# DAC_and_MIC.net
KiCad netlist of a schematic drawn in Altium Designer
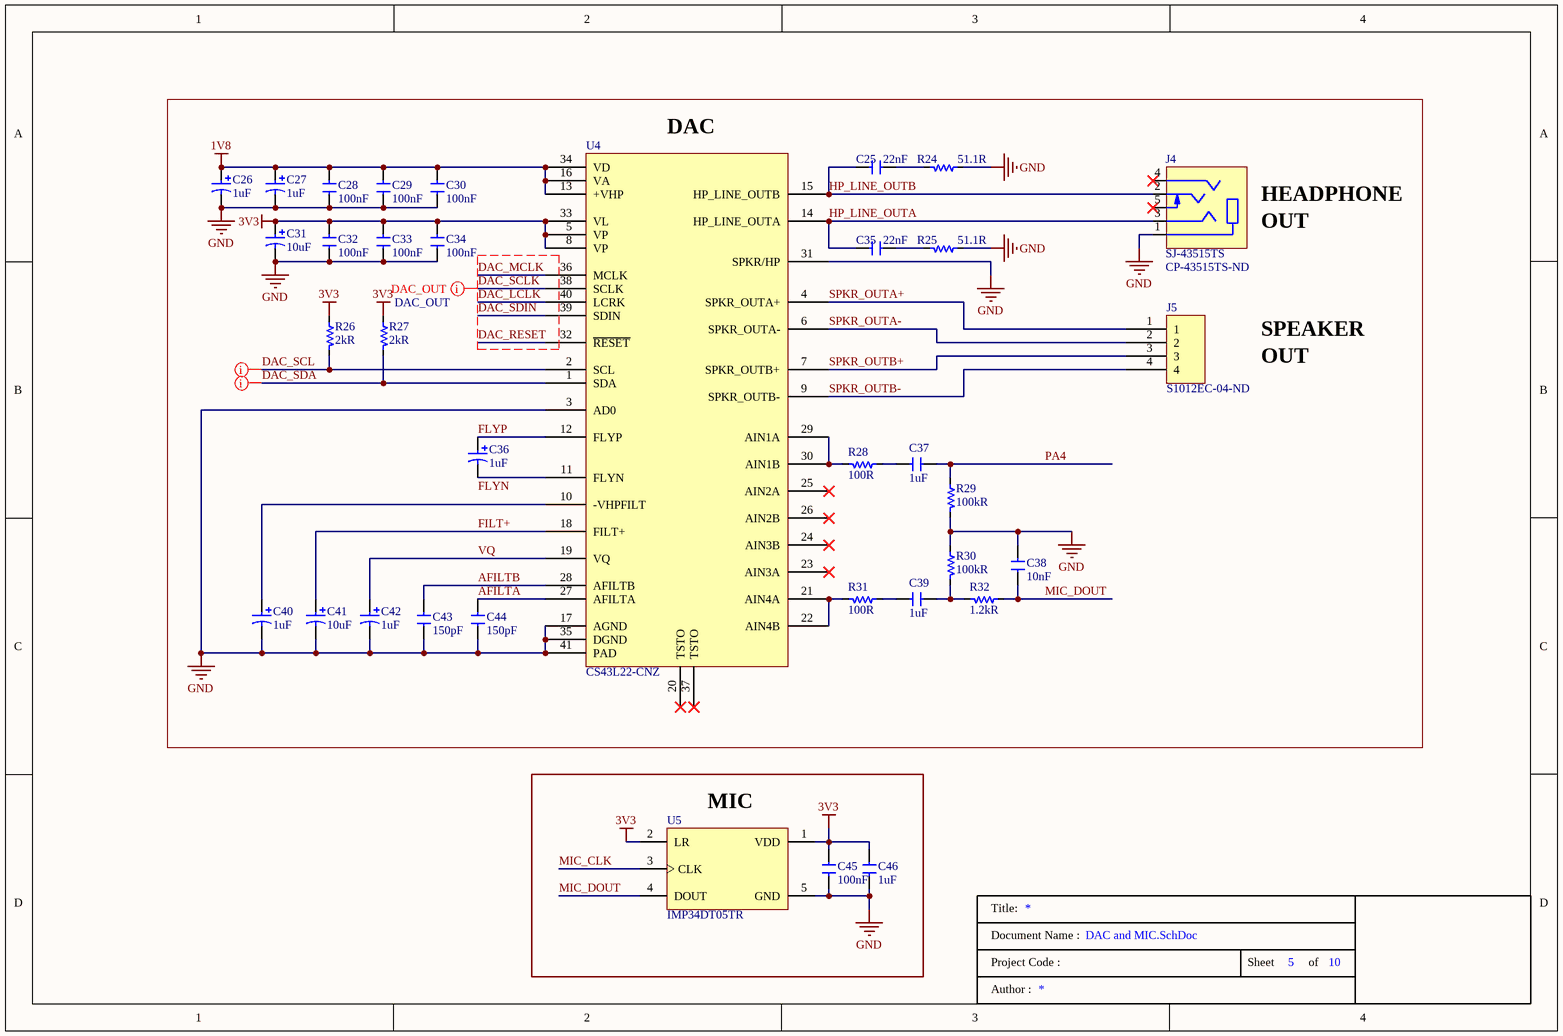
[diagram p0: DAC and MIC.SchDoc]

(export (version "E")
  (design (tool "Eeschema 10.0.6"))
  (components
    (comp (ref "C25")
      (value "CAP_22nF_50V_0805_X7R_CER")
      (footprint "0805_CAP")
      (description "Cap Ceramic 0.022uF 50V X7R 10% Pad SMD 0805 125C T/R")
      (fields
        (field (name "MANUFACTURER") "KEMET")
        (field (name "MANUFACTURER PART NUMBER") "C0805C223K5RAC7210")
        (field (name "CAPACITANCE") "22nF")
      )
      (libsource (lib "Main Component Library") (part "CAP_22nF_50V_0805_X7R_CER"))
    )
    (comp (ref "C26")
      (value "CAP_1uF_10%_16V_1206_TANT")
      (footprint "1206_TANT_CAP")
      (description "CAP TANT 1UF 10% 16V 1206")
      (fields
        (field (name "MANUFACTURER") "Kyocera AVX")
        (field (name "MANUFACTURER PART NUMBER") "TAJA105K016SNJ")
        (field (name "CAPACITANCE") "1uF")
      )
      (libsource (lib "Main Component Library") (part "CAP_1uF_10%_16V_1206_TANT"))
    )
    (comp (ref "C27")
      (value "CAP_1uF_10%_16V_1206_TANT")
      (footprint "1206_TANT_CAP")
      (description "CAP TANT 1UF 10% 16V 1206")
      (fields
        (field (name "MANUFACTURER") "Kyocera AVX")
        (field (name "MANUFACTURER PART NUMBER") "TAJA105K016SNJ")
        (field (name "CAPACITANCE") "1uF")
      )
      (libsource (lib "Main Component Library") (part "CAP_1uF_10%_16V_1206_TANT"))
    )
    (comp (ref "C28")
      (value "CAP_0.1uF_50V_0805_X7R_CER")
      (footprint "0805_CAP")
      (description "Cap Ceramic 0.1uF 50V X7R 20% SMD 0805 125C Paper T/R")
      (fields
        (field (name "MANUFACTURER") "KEMET")
        (field (name "MANUFACTURER PART NUMBER") "C0805C104M5RACTU")
        (field (name "CAPACITANCE") "100nF")
      )
      (libsource (lib "Main Component Library") (part "CAP_0.1uF_50V_0805_X7R_CER"))
    )
    (comp (ref "C29")
      (value "CAP_0.1uF_50V_0805_X7R_CER")
      (footprint "0805_CAP")
      (description "Cap Ceramic 0.1uF 50V X7R 20% SMD 0805 125C Paper T/R")
      (fields
        (field (name "MANUFACTURER") "KEMET")
        (field (name "MANUFACTURER PART NUMBER") "C0805C104M5RACTU")
        (field (name "CAPACITANCE") "100nF")
      )
      (libsource (lib "Main Component Library") (part "CAP_0.1uF_50V_0805_X7R_CER"))
    )
    (comp (ref "C30")
      (value "CAP_0.1uF_50V_0805_X7R_CER")
      (footprint "0805_CAP")
      (description "Cap Ceramic 0.1uF 50V X7R 20% SMD 0805 125C Paper T/R")
      (fields
        (field (name "MANUFACTURER") "KEMET")
        (field (name "MANUFACTURER PART NUMBER") "C0805C104M5RACTU")
        (field (name "CAPACITANCE") "100nF")
      )
      (libsource (lib "Main Component Library") (part "CAP_0.1uF_50V_0805_X7R_CER"))
    )
    (comp (ref "C31")
      (value "CAP_10uF_10V_10%_1206_TANT")
      (footprint "1206_TANT_CAP")
      (description "Cap Tant Solid 10uF 10V A CASE 10% (3.2 X 1.6 X 1.6mm) Inward L SMD 3216-18 3 Ohm 125C T/R")
      (fields
        (field (name "MANUFACTURER") "Kyocera AVX")
        (field (name "MANUFACTURER PART NUMBER") "TAJA106K010SNJ")
        (field (name "CAPACITANCE") "10uF")
      )
      (libsource (lib "Main Component Library") (part "CAP_10uF_10V_10%_1206_TANT"))
    )
    (comp (ref "C32")
      (value "CAP_0.1uF_50V_0805_X7R_CER")
      (footprint "0805_CAP")
      (description "Cap Ceramic 0.1uF 50V X7R 20% SMD 0805 125C Paper T/R")
      (fields
        (field (name "MANUFACTURER") "KEMET")
        (field (name "MANUFACTURER PART NUMBER") "C0805C104M5RACTU")
        (field (name "CAPACITANCE") "100nF")
      )
      (libsource (lib "Main Component Library") (part "CAP_0.1uF_50V_0805_X7R_CER"))
    )
    (comp (ref "C33")
      (value "CAP_0.1uF_50V_0805_X7R_CER")
      (footprint "0805_CAP")
      (description "Cap Ceramic 0.1uF 50V X7R 20% SMD 0805 125C Paper T/R")
      (fields
        (field (name "MANUFACTURER") "KEMET")
        (field (name "MANUFACTURER PART NUMBER") "C0805C104M5RACTU")
        (field (name "CAPACITANCE") "100nF")
      )
      (libsource (lib "Main Component Library") (part "CAP_0.1uF_50V_0805_X7R_CER"))
    )
    (comp (ref "C34")
      (value "CAP_0.1uF_50V_0805_X7R_CER")
      (footprint "0805_CAP")
      (description "Cap Ceramic 0.1uF 50V X7R 20% SMD 0805 125C Paper T/R")
      (fields
        (field (name "MANUFACTURER") "KEMET")
        (field (name "MANUFACTURER PART NUMBER") "C0805C104M5RACTU")
        (field (name "CAPACITANCE") "100nF")
      )
      (libsource (lib "Main Component Library") (part "CAP_0.1uF_50V_0805_X7R_CER"))
    )
    (comp (ref "C35")
      (value "CAP_22nF_50V_0805_X7R_CER")
      (footprint "0805_CAP")
      (description "Cap Ceramic 0.022uF 50V X7R 10% Pad SMD 0805 125C T/R")
      (fields
        (field (name "MANUFACTURER") "KEMET")
        (field (name "MANUFACTURER PART NUMBER") "C0805C223K5RAC7210")
        (field (name "CAPACITANCE") "22nF")
      )
      (libsource (lib "Main Component Library") (part "CAP_22nF_50V_0805_X7R_CER"))
    )
    (comp (ref "C36")
      (value "CAP_1uF_10%_16V_1206_TANT")
      (footprint "1206_TANT_CAP")
      (description "CAP TANT 1UF 10% 16V 1206")
      (fields
        (field (name "MANUFACTURER") "Kyocera AVX")
        (field (name "MANUFACTURER PART NUMBER") "TAJA105K016SNJ")
        (field (name "CAPACITANCE") "1uF")
      )
      (libsource (lib "Main Component Library") (part "CAP_1uF_10%_16V_1206_TANT"))
    )
    (comp (ref "C37")
      (value "1uF")
      (footprint "0805_CAP")
      (description "陶瓷电容 1uF(105) 1uF ±10% 25V 0805")
      (fields
        (field (name "MANUFACTURER") "Samsung")
        (field (name "MANUFACTURER PART NUMBER") "CL21B105KAFNNNG")
      )
      (libsource (lib "Main Schematic Library") (part "CAP_1uF_%10_25V_0805_X7R_CER"))
    )
    (comp (ref "C38")
      (value "CAP_10nF_%10_50V_0805_X7R_CER")
      (footprint "0805_CAP")
      (description "CAP CER 10000PF 50V X7R 0805")
      (fields
        (field (name "MANUFACTURER") "Samsung")
        (field (name "MANUFACTURER PART NUMBER") "CL21B103KBANNNC")
        (field (name "CAPACITANCE") "10nF")
      )
      (libsource (lib "Main Schematic Library") (part "CAP_10nF_%10_50V_0805_X7R_CER"))
    )
    (comp (ref "C39")
      (value "1uF")
      (footprint "0805_CAP")
      (description "陶瓷电容 1uF(105) 1uF ±10% 25V 0805")
      (fields
        (field (name "MANUFACTURER") "Samsung")
        (field (name "MANUFACTURER PART NUMBER") "CL21B105KAFNNNG")
      )
      (libsource (lib "Main Schematic Library") (part "CAP_1uF_%10_25V_0805_X7R_CER"))
    )
    (comp (ref "C40")
      (value "CAP_1uF_10%_16V_1206_TANT")
      (footprint "1206_TANT_CAP")
      (description "CAP TANT 1UF 10% 16V 1206")
      (fields
        (field (name "MANUFACTURER") "Kyocera AVX")
        (field (name "MANUFACTURER PART NUMBER") "TAJA105K016SNJ")
        (field (name "CAPACITANCE") "1uF")
      )
      (libsource (lib "Main Component Library") (part "CAP_1uF_10%_16V_1206_TANT"))
    )
    (comp (ref "C41")
      (value "CAP_10uF_10V_10%_1206_TANT")
      (footprint "1206_TANT_CAP")
      (description "Cap Tant Solid 10uF 10V A CASE 10% (3.2 X 1.6 X 1.6mm) Inward L SMD 3216-18 3 Ohm 125C T/R")
      (fields
        (field (name "MANUFACTURER") "Kyocera AVX")
        (field (name "MANUFACTURER PART NUMBER") "TAJA106K010SNJ")
        (field (name "CAPACITANCE") "10uF")
      )
      (libsource (lib "Main Component Library") (part "CAP_10uF_10V_10%_1206_TANT"))
    )
    (comp (ref "C42")
      (value "CAP_1uF_10%_16V_1206_TANT")
      (footprint "1206_TANT_CAP")
      (description "CAP TANT 1UF 10% 16V 1206")
      (fields
        (field (name "MANUFACTURER") "Kyocera AVX")
        (field (name "MANUFACTURER PART NUMBER") "TAJA105K016SNJ")
        (field (name "CAPACITANCE") "1uF")
      )
      (libsource (lib "Main Component Library") (part "CAP_1uF_10%_16V_1206_TANT"))
    )
    (comp (ref "C43")
      (value "CAP_150pF_%5_50V_0805_C0G/NP0_CER")
      (footprint "0805_CAP")
      (description "陶瓷电容 150pF(151) 150pF ±5% 50V C0G(NP0) 0805")
      (fields
        (field (name "MANUFACTURER") "KEMET")
        (field (name "MANUFACTURER PART NUMBER") "C0805C151J5GACTU")
        (field (name "CAPACITANCE") "150pF")
      )
      (libsource (lib "Main Schematic Library") (part "CAP_150pF_%5_50V_0805_C0G/NP0_CER"))
    )
    (comp (ref "C44")
      (value "CAP_150pF_%5_50V_0805_C0G/NP0_CER")
      (footprint "0805_CAP")
      (description "陶瓷电容 150pF(151) 150pF ±5% 50V C0G(NP0) 0805")
      (fields
        (field (name "MANUFACTURER") "KEMET")
        (field (name "MANUFACTURER PART NUMBER") "C0805C151J5GACTU")
        (field (name "CAPACITANCE") "150pF")
      )
      (libsource (lib "Main Schematic Library") (part "CAP_150pF_%5_50V_0805_C0G/NP0_CER"))
    )
    (comp (ref "C45")
      (value "CAP_0.1uF_50V_0805_X7R_CER")
      (footprint "0805_CAP")
      (description "Cap Ceramic 0.1uF 50V X7R 20% SMD 0805 125C Paper T/R")
      (fields
        (field (name "MANUFACTURER") "KEMET")
        (field (name "MANUFACTURER PART NUMBER") "C0805C104M5RACTU")
        (field (name "CAPACITANCE") "100nF")
      )
      (libsource (lib "Main Component Library") (part "CAP_0.1uF_50V_0805_X7R_CER"))
    )
    (comp (ref "C46")
      (value "1uF")
      (footprint "0805_CAP")
      (description "陶瓷电容 1uF(105) 1uF ±10% 25V 0805")
      (fields
        (field (name "MANUFACTURER") "Samsung")
        (field (name "MANUFACTURER PART NUMBER") "CL21B105KAFNNNG")
      )
      (libsource (lib "Main Schematic Library") (part "CAP_1uF_%10_25V_0805_X7R_CER"))
    )
    (comp (ref "J4")
      (value "SJ-43515TS")
      (footprint "CONN TRSS HEADPHONE JACK")
      (description "Conn 3.5MM Audio Jack RCP 5 POS RA Thru-Hole 5 Terminal 1 Port")
      (fields
        (field (name "MANUFACTURER") "CUI Devices")
        (field (name "SUPPLIER PART NUMBER 1") "CP-43515TS-ND")
      )
      (libsource (lib "Main Component Library") (part "CONN_JACK_4COND_3.5MM_R/A"))
    )
    (comp (ref "J5")
      (value "CONN_1X4_2.54mm_Male Header")
      (footprint "DIP_1X4_MALE_HEADER_2.54_PITCH")
      (description "Connector Header Through Hole 4 position 0.100\" (2.54mm)")
      (fields
        (field (name "MANUFACTURER") "Sullins")
        (field (name "MANUFACTURER PART NUMBER") "PREC004SAAN-RC")
        (field (name "SUPPLIER PART NUMBER 1") "S1012EC-04-ND")
      )
      (libsource (lib "Main Schematic Library") (part "CONN_1X4_2.54mm_Male Header"))
    )
    (comp (ref "R24")
      (value "RES_51.1 OHM_1%_0805_1/8W")
      (footprint "0805_RES")
      (description "贴片电阻 51.1Ω ± 1.00% 0.125W ± 100ppm/℃ 0805")
      (fields
        (field (name "MANUFACTURER") "Yageo")
        (field (name "MANUFACTURER PART NUMBER") "RC0805FR-0751R1L")
        (field (name "RESISTANCE") "51.1R")
      )
      (libsource (lib "Main Component Library") (part "RES_51.1 OHM_1%_0805_1/8W"))
    )
    (comp (ref "R25")
      (value "RES_51.1 OHM_1%_0805_1/8W")
      (footprint "0805_RES")
      (description "贴片电阻 51.1Ω ± 1.00% 0.125W ± 100ppm/℃ 0805")
      (fields
        (field (name "MANUFACTURER") "Yageo")
        (field (name "MANUFACTURER PART NUMBER") "RC0805FR-0751R1L")
        (field (name "RESISTANCE") "51.1R")
      )
      (libsource (lib "Main Component Library") (part "RES_51.1 OHM_1%_0805_1/8W"))
    )
    (comp (ref "R26")
      (value "RES_2K OHM_1%_0805_1/8W_SMD")
      (footprint "0805_RES")
      (description "Res Thick Film 0805 2K Ohm 1% 0.125W(1/8W) ±100ppm/C Pad SMD Automotive T/R")
      (fields
        (field (name "MANUFACTURER") "Yageo")
        (field (name "MANUFACTURER PART NUMBER") "AC0805FR-072KL")
        (field (name "RESISTANCE") "2kR")
      )
      (libsource (lib "Main Component Library") (part "RES_2K OHM_1%_0805_1/8W_SMD"))
    )
    (comp (ref "R27")
      (value "RES_2K OHM_1%_0805_1/8W_SMD")
      (footprint "0805_RES")
      (description "Res Thick Film 0805 2K Ohm 1% 0.125W(1/8W) ±100ppm/C Pad SMD Automotive T/R")
      (fields
        (field (name "MANUFACTURER") "Yageo")
        (field (name "MANUFACTURER PART NUMBER") "AC0805FR-072KL")
        (field (name "RESISTANCE") "2kR")
      )
      (libsource (lib "Main Component Library") (part "RES_2K OHM_1%_0805_1/8W_SMD"))
    )
    (comp (ref "R28")
      (value "RES_100 OHM_1%_0805_1/8W")
      (footprint "0805_RES")
      (description "贴片电阻 100Ω ± 1.00% 0.125W ± 100ppm/℃ 0805")
      (fields
        (field (name "MANUFACTURER") "Yageo")
        (field (name "MANUFACTURER PART NUMBER") "RC0805FR-07100RL")
        (field (name "RESISTANCE") "100R")
      )
      (libsource (lib "Main Schematic Library") (part "RES_100 OHM_1%_0805_1/8W"))
    )
    (comp (ref "R29")
      (value "100kR")
      (footprint "0805_RES")
      (fields
        (field (name "MANUFACTURER") "Vishay")
        (field (name "MANUFACTURER PART NUMBER") "CRCW0805100KFKEBC")
        (field (name "TOLERANCE") "1%")
      )
      (libsource (lib "Main Schematic Library") (part "RES_100K OHM_1%_0805_1/8W"))
    )
    (comp (ref "R30")
      (value "100kR")
      (footprint "0805_RES")
      (fields
        (field (name "MANUFACTURER") "Vishay")
        (field (name "MANUFACTURER PART NUMBER") "CRCW0805100KFKEBC")
        (field (name "TOLERANCE") "1%")
      )
      (libsource (lib "Main Schematic Library") (part "RES_100K OHM_1%_0805_1/8W"))
    )
    (comp (ref "R31")
      (value "RES_100 OHM_1%_0805_1/8W")
      (footprint "0805_RES")
      (description "贴片电阻 100Ω ± 1.00% 0.125W ± 100ppm/℃ 0805")
      (fields
        (field (name "MANUFACTURER") "Yageo")
        (field (name "MANUFACTURER PART NUMBER") "RC0805FR-07100RL")
        (field (name "RESISTANCE") "100R")
      )
      (libsource (lib "Main Schematic Library") (part "RES_100 OHM_1%_0805_1/8W"))
    )
    (comp (ref "R32")
      (value "1.2kR")
      (footprint "0805_RES")
      (description "Res Thick Film 0805 1.2K Ohm 1% 1/8W ±100ppm/°C Molded SMD Paper T/R")
      (fields
        (field (name "MANUFACTURER") "Vishay Semiconductors")
        (field (name "MANUFACTURER PART NUMBER") "CRCW08051K20FKEAC")
      )
      (libsource (lib "Main Schematic Library") (part "RES_1.2K OHM_1%_0805_1/8W"))
    )
    (comp (ref "U4")
      (value "IC_CODEC_CS43L22")
      (footprint "QFN50P600X600X100_HS-41N")
      (description "DAC 1-CH Delta-Sigma 24-bit 40-Pin QFN EP Rail")
      (fields
        (field (name "MANUFACTURER") "Cirrus Logic")
        (field (name "MANUFACTURER PART NUMBER") "CS43L22-CNZ")
      )
      (libsource (lib "Main Schematic Library") (part "IC_CODEC_CS43L22"))
    )
    (comp (ref "U5")
      (value "IMP34DT05TR")
      (footprint "MIC_IMP34DT05TR")
      (description "IMP34DT05: 3.6V MEMS Audio Sensor Omnidirectional Digital Microphone - HCLGA-4LD")
      (fields (field (name "MANUFACTURER") "STMicroelectronics"))
      (libsource (lib "Main Schematic Library") (part "MIC_IMP34DT05TR"))
    )
  )
  (nets
    (net (code "1") (name "/AFILTA") (class "Default")
      (node (ref "C44") (pin "2") (pinfunction "2_2") (pintype "passive"))
      (node (ref "U4") (pin "27") (pinfunction "AFILTA_27") (pintype "passive"))
    )
    (net (code "2") (name "/AFILTB") (class "Default")
      (node (ref "C43") (pin "2") (pinfunction "2_2") (pintype "passive"))
      (node (ref "U4") (pin "28") (pinfunction "AFILTB_28") (pintype "passive"))
    )
    (net (code "3") (name "/DAC_LCLK") (class "Default")
      (node (ref "U4") (pin "40") (pinfunction "LCRK_40") (pintype "passive"))
    )
    (net (code "4") (name "/DAC_MCLK") (class "Default")
      (node (ref "U4") (pin "36") (pinfunction "MCLK_36") (pintype "passive"))
    )
    (net (code "5") (name "/DAC_RESET") (class "Default")
      (node (ref "U4") (pin "32") (pinfunction "~{RESET}_32") (pintype "passive"))
    )
    (net (code "6") (name "/DAC_SCL") (class "Default")
      (node (ref "R26") (pin "1") (pinfunction "1_1") (pintype "passive"))
      (node (ref "U4") (pin "2") (pinfunction "SCL_2") (pintype "passive"))
    )
    (net (code "7") (name "/DAC_SCLK") (class "Default")
      (node (ref "U4") (pin "38") (pinfunction "SCLK_38") (pintype "passive"))
    )
    (net (code "8") (name "/DAC_SDA") (class "Default")
      (node (ref "R27") (pin "1") (pinfunction "1_1") (pintype "passive"))
      (node (ref "U4") (pin "1") (pinfunction "SDA_1") (pintype "passive"))
    )
    (net (code "9") (name "/DAC_SDIN") (class "Default")
      (node (ref "U4") (pin "39") (pinfunction "SDIN_39") (pintype "passive"))
    )
    (net (code "10") (name "/FILT+") (class "Default")
      (node (ref "C41") (pin "1") (pinfunction "1_1") (pintype "passive"))
      (node (ref "U4") (pin "18") (pinfunction "FILT+_18") (pintype "passive"))
    )
    (net (code "11") (name "/FLYN") (class "Default")
      (node (ref "C36") (pin "2") (pinfunction "2_2") (pintype "passive"))
      (node (ref "U4") (pin "11") (pinfunction "FLYN_11") (pintype "passive"))
    )
    (net (code "12") (name "/FLYP") (class "Default")
      (node (ref "C36") (pin "1") (pinfunction "1_1") (pintype "passive"))
      (node (ref "U4") (pin "12") (pinfunction "FLYP_12") (pintype "passive"))
    )
    (net (code "13") (name "/HP_LINE_OUTA") (class "Default")
      (node (ref "C35") (pin "1") (pinfunction "1_1") (pintype "passive"))
      (node (ref "J4") (pin "3") (pinfunction "RING1_3") (pintype "passive"))
      (node (ref "U4") (pin "14") (pinfunction "HP_LINE_OUTA_14") (pintype "passive"))
    )
    (net (code "14") (name "/HP_LINE_OUTB") (class "Default")
      (node (ref "C25") (pin "1") (pinfunction "1_1") (pintype "passive"))
      (node (ref "J4") (pin "2") (pinfunction "TIP_2") (pintype "passive"))
      (node (ref "U4") (pin "15") (pinfunction "HP_LINE_OUTB_15") (pintype "passive"))
    )
    (net (code "15") (name "/MIC_CLK") (class "Default")
      (node (ref "U5") (pin "3") (pinfunction "CLK_3") (pintype "passive"))
    )
    (net (code "16") (name "/MIC_DOUT") (class "Default")
      (node (ref "C38") (pin "2") (pinfunction "2_2") (pintype "passive"))
      (node (ref "R32") (pin "2") (pinfunction "2_2") (pintype "passive"))
      (node (ref "U5") (pin "4") (pinfunction "DOUT_4") (pintype "passive"))
    )
    (net (code "17") (name "/PA4") (class "Default")
      (node (ref "C37") (pin "2") (pinfunction "2_2") (pintype "passive"))
      (node (ref "R29") (pin "2") (pinfunction "2_2") (pintype "passive"))
    )
    (net (code "18") (name "/SPKR_OUTA+") (class "Default")
      (node (ref "J5") (pin "1") (pinfunction "1_1") (pintype "passive"))
      (node (ref "U4") (pin "4") (pinfunction "SPKR_OUTA+_4") (pintype "passive"))
    )
    (net (code "19") (name "/SPKR_OUTA-") (class "Default")
      (node (ref "J5") (pin "2") (pinfunction "2_2") (pintype "passive"))
      (node (ref "U4") (pin "6") (pinfunction "SPKR_OUTA-_6") (pintype "passive"))
    )
    (net (code "20") (name "/SPKR_OUTB+") (class "Default")
      (node (ref "J5") (pin "3") (pinfunction "3_3") (pintype "passive"))
      (node (ref "U4") (pin "7") (pinfunction "SPKR_OUTB+_7") (pintype "passive"))
    )
    (net (code "21") (name "/SPKR_OUTB-") (class "Default")
      (node (ref "J5") (pin "4") (pinfunction "4_4") (pintype "passive"))
      (node (ref "U4") (pin "9") (pinfunction "SPKR_OUTB-_9") (pintype "passive"))
    )
    (net (code "22") (name "/VQ") (class "Default")
      (node (ref "C42") (pin "1") (pinfunction "1_1") (pintype "passive"))
      (node (ref "U4") (pin "19") (pinfunction "VQ_19") (pintype "passive"))
    )
    (net (code "23") (name "1V8") (class "Default")
      (node (ref "C26") (pin "1") (pinfunction "1_1") (pintype "passive"))
      (node (ref "C27") (pin "1") (pinfunction "1_1") (pintype "passive"))
      (node (ref "C28") (pin "2") (pinfunction "2_2") (pintype "passive"))
      (node (ref "C29") (pin "2") (pinfunction "2_2") (pintype "passive"))
      (node (ref "C30") (pin "2") (pinfunction "2_2") (pintype "passive"))
      (node (ref "U4") (pin "13") (pinfunction "+VHP_13") (pintype "passive"))
      (node (ref "U4") (pin "16") (pinfunction "VA_16") (pintype "passive"))
      (node (ref "U4") (pin "34") (pinfunction "VD_34") (pintype "passive"))
    )
    (net (code "24") (name "3V3") (class "Default")
      (node (ref "C31") (pin "1") (pinfunction "1_1") (pintype "passive"))
      (node (ref "C32") (pin "2") (pinfunction "2_2") (pintype "passive"))
      (node (ref "C33") (pin "2") (pinfunction "2_2") (pintype "passive"))
      (node (ref "C34") (pin "2") (pinfunction "2_2") (pintype "passive"))
      (node (ref "C45") (pin "2") (pinfunction "2_2") (pintype "passive"))
      (node (ref "C46") (pin "2") (pinfunction "2_2") (pintype "passive"))
      (node (ref "R26") (pin "2") (pinfunction "2_2") (pintype "passive"))
      (node (ref "R27") (pin "2") (pinfunction "2_2") (pintype "passive"))
      (node (ref "U4") (pin "33") (pinfunction "VL_33") (pintype "passive"))
      (node (ref "U4") (pin "5") (pinfunction "VP_5") (pintype "passive"))
      (node (ref "U4") (pin "8") (pinfunction "VP_8") (pintype "passive"))
      (node (ref "U5") (pin "1") (pinfunction "VDD_1") (pintype "passive"))
      (node (ref "U5") (pin "2") (pinfunction "LR_2") (pintype "passive"))
    )
    (net (code "25") (name "GND") (class "Default")
      (node (ref "C26") (pin "2") (pinfunction "2_2") (pintype "passive"))
      (node (ref "C27") (pin "2") (pinfunction "2_2") (pintype "passive"))
      (node (ref "C28") (pin "1") (pinfunction "1_1") (pintype "passive"))
      (node (ref "C29") (pin "1") (pinfunction "1_1") (pintype "passive"))
      (node (ref "C30") (pin "1") (pinfunction "1_1") (pintype "passive"))
      (node (ref "C31") (pin "2") (pinfunction "2_2") (pintype "passive"))
      (node (ref "C32") (pin "1") (pinfunction "1_1") (pintype "passive"))
      (node (ref "C33") (pin "1") (pinfunction "1_1") (pintype "passive"))
      (node (ref "C34") (pin "1") (pinfunction "1_1") (pintype "passive"))
      (node (ref "C38") (pin "1") (pinfunction "1_1") (pintype "passive"))
      (node (ref "C40") (pin "2") (pinfunction "2_2") (pintype "passive"))
      (node (ref "C41") (pin "2") (pinfunction "2_2") (pintype "passive"))
      (node (ref "C42") (pin "2") (pinfunction "2_2") (pintype "passive"))
      (node (ref "C43") (pin "1") (pinfunction "1_1") (pintype "passive"))
      (node (ref "C44") (pin "1") (pinfunction "1_1") (pintype "passive"))
      (node (ref "C45") (pin "1") (pinfunction "1_1") (pintype "passive"))
      (node (ref "C46") (pin "1") (pinfunction "1_1") (pintype "passive"))
      (node (ref "J4") (pin "1") (pinfunction "SLEEVE_1") (pintype "passive"))
      (node (ref "R24") (pin "2") (pinfunction "2_2") (pintype "passive"))
      (node (ref "R25") (pin "2") (pinfunction "2_2") (pintype "passive"))
      (node (ref "R29") (pin "1") (pinfunction "1_1") (pintype "passive"))
      (node (ref "R30") (pin "2") (pinfunction "2_2") (pintype "passive"))
      (node (ref "U4") (pin "17") (pinfunction "AGND_17") (pintype "passive"))
      (node (ref "U4") (pin "3") (pinfunction "AD0_3") (pintype "passive"))
      (node (ref "U4") (pin "31") (pinfunction "SPKR/HP_31") (pintype "passive"))
      (node (ref "U4") (pin "35") (pinfunction "DGND_35") (pintype "passive"))
      (node (ref "U4") (pin "41") (pinfunction "PAD_41") (pintype "passive"))
      (node (ref "U5") (pin "5") (pinfunction "GND_5") (pintype "passive"))
    )
    (net (code "26") (name "Net-(C25-Pad2)") (class "Default")
      (node (ref "C25") (pin "2") (pinfunction "2_2") (pintype "passive"))
      (node (ref "R24") (pin "1") (pinfunction "1_1") (pintype "passive"))
    )
    (net (code "27") (name "Net-(C35-Pad2)") (class "Default")
      (node (ref "C35") (pin "2") (pinfunction "2_2") (pintype "passive"))
      (node (ref "R25") (pin "1") (pinfunction "1_1") (pintype "passive"))
    )
    (net (code "28") (name "Net-(C37-Pad1)") (class "Default")
      (node (ref "C37") (pin "1") (pinfunction "1_1") (pintype "passive"))
      (node (ref "R28") (pin "2") (pinfunction "2_2") (pintype "passive"))
    )
    (net (code "29") (name "Net-(C39-Pad1)") (class "Default")
      (node (ref "C39") (pin "1") (pinfunction "1_1") (pintype "passive"))
      (node (ref "R31") (pin "2") (pinfunction "2_2") (pintype "passive"))
    )
    (net (code "30") (name "Net-(C39-Pad2)") (class "Default")
      (node (ref "C39") (pin "2") (pinfunction "2_2") (pintype "passive"))
      (node (ref "R30") (pin "1") (pinfunction "1_1") (pintype "passive"))
      (node (ref "R32") (pin "1") (pinfunction "1_1") (pintype "passive"))
    )
    (net (code "31") (name "Net-(U4--VHPFILT)") (class "Default")
      (node (ref "C40") (pin "1") (pinfunction "1_1") (pintype "passive"))
      (node (ref "U4") (pin "10") (pinfunction "-VHPFILT_10") (pintype "passive"))
    )
    (net (code "32") (name "Net-(U4-AIN1A)") (class "Default")
      (node (ref "R28") (pin "1") (pinfunction "1_1") (pintype "passive"))
      (node (ref "U4") (pin "29") (pinfunction "AIN1A_29") (pintype "passive"))
      (node (ref "U4") (pin "30") (pinfunction "AIN1B_30") (pintype "passive"))
    )
    (net (code "33") (name "Net-(U4-AIN4A)") (class "Default")
      (node (ref "R31") (pin "1") (pinfunction "1_1") (pintype "passive"))
      (node (ref "U4") (pin "21") (pinfunction "AIN4A_21") (pintype "passive"))
      (node (ref "U4") (pin "22") (pinfunction "AIN4B_22") (pintype "passive"))
    )
    (net (code "34") (name "unconnected-(J4-RING2-Pad4)") (class "Default")
      (node (ref "J4") (pin "4") (pinfunction "RING2_4") (pintype "passive+no_connect"))
    )
    (net (code "35") (name "unconnected-(J4-TIP_SWITCH-Pad5)") (class "Default")
      (node (ref "J4") (pin "5") (pinfunction "TIP_SWITCH_5") (pintype "passive+no_connect"))
    )
    (net (code "36") (name "unconnected-(U4-AIN2A-Pad25)") (class "Default")
      (node (ref "U4") (pin "25") (pinfunction "AIN2A_25") (pintype "passive+no_connect"))
    )
    (net (code "37") (name "unconnected-(U4-AIN2B-Pad26)") (class "Default")
      (node (ref "U4") (pin "26") (pinfunction "AIN2B_26") (pintype "passive+no_connect"))
    )
    (net (code "38") (name "unconnected-(U4-AIN3A-Pad23)") (class "Default")
      (node (ref "U4") (pin "23") (pinfunction "AIN3A_23") (pintype "passive+no_connect"))
    )
    (net (code "39") (name "unconnected-(U4-AIN3B-Pad24)") (class "Default")
      (node (ref "U4") (pin "24") (pinfunction "AIN3B_24") (pintype "passive+no_connect"))
    )
    (net (code "40") (name "unconnected-(U4-TSTO-Pad20)") (class "Default")
      (node (ref "U4") (pin "20") (pinfunction "TSTO_20") (pintype "passive+no_connect"))
    )
    (net (code "41") (name "unconnected-(U4-TSTO-Pad37)") (class "Default")
      (node (ref "U4") (pin "37") (pinfunction "TSTO_37") (pintype "passive+no_connect"))
    )
  )
)
